# pcb-pick-plaz-led.net
KiCad netlist of a schematic drawn in EAGLE
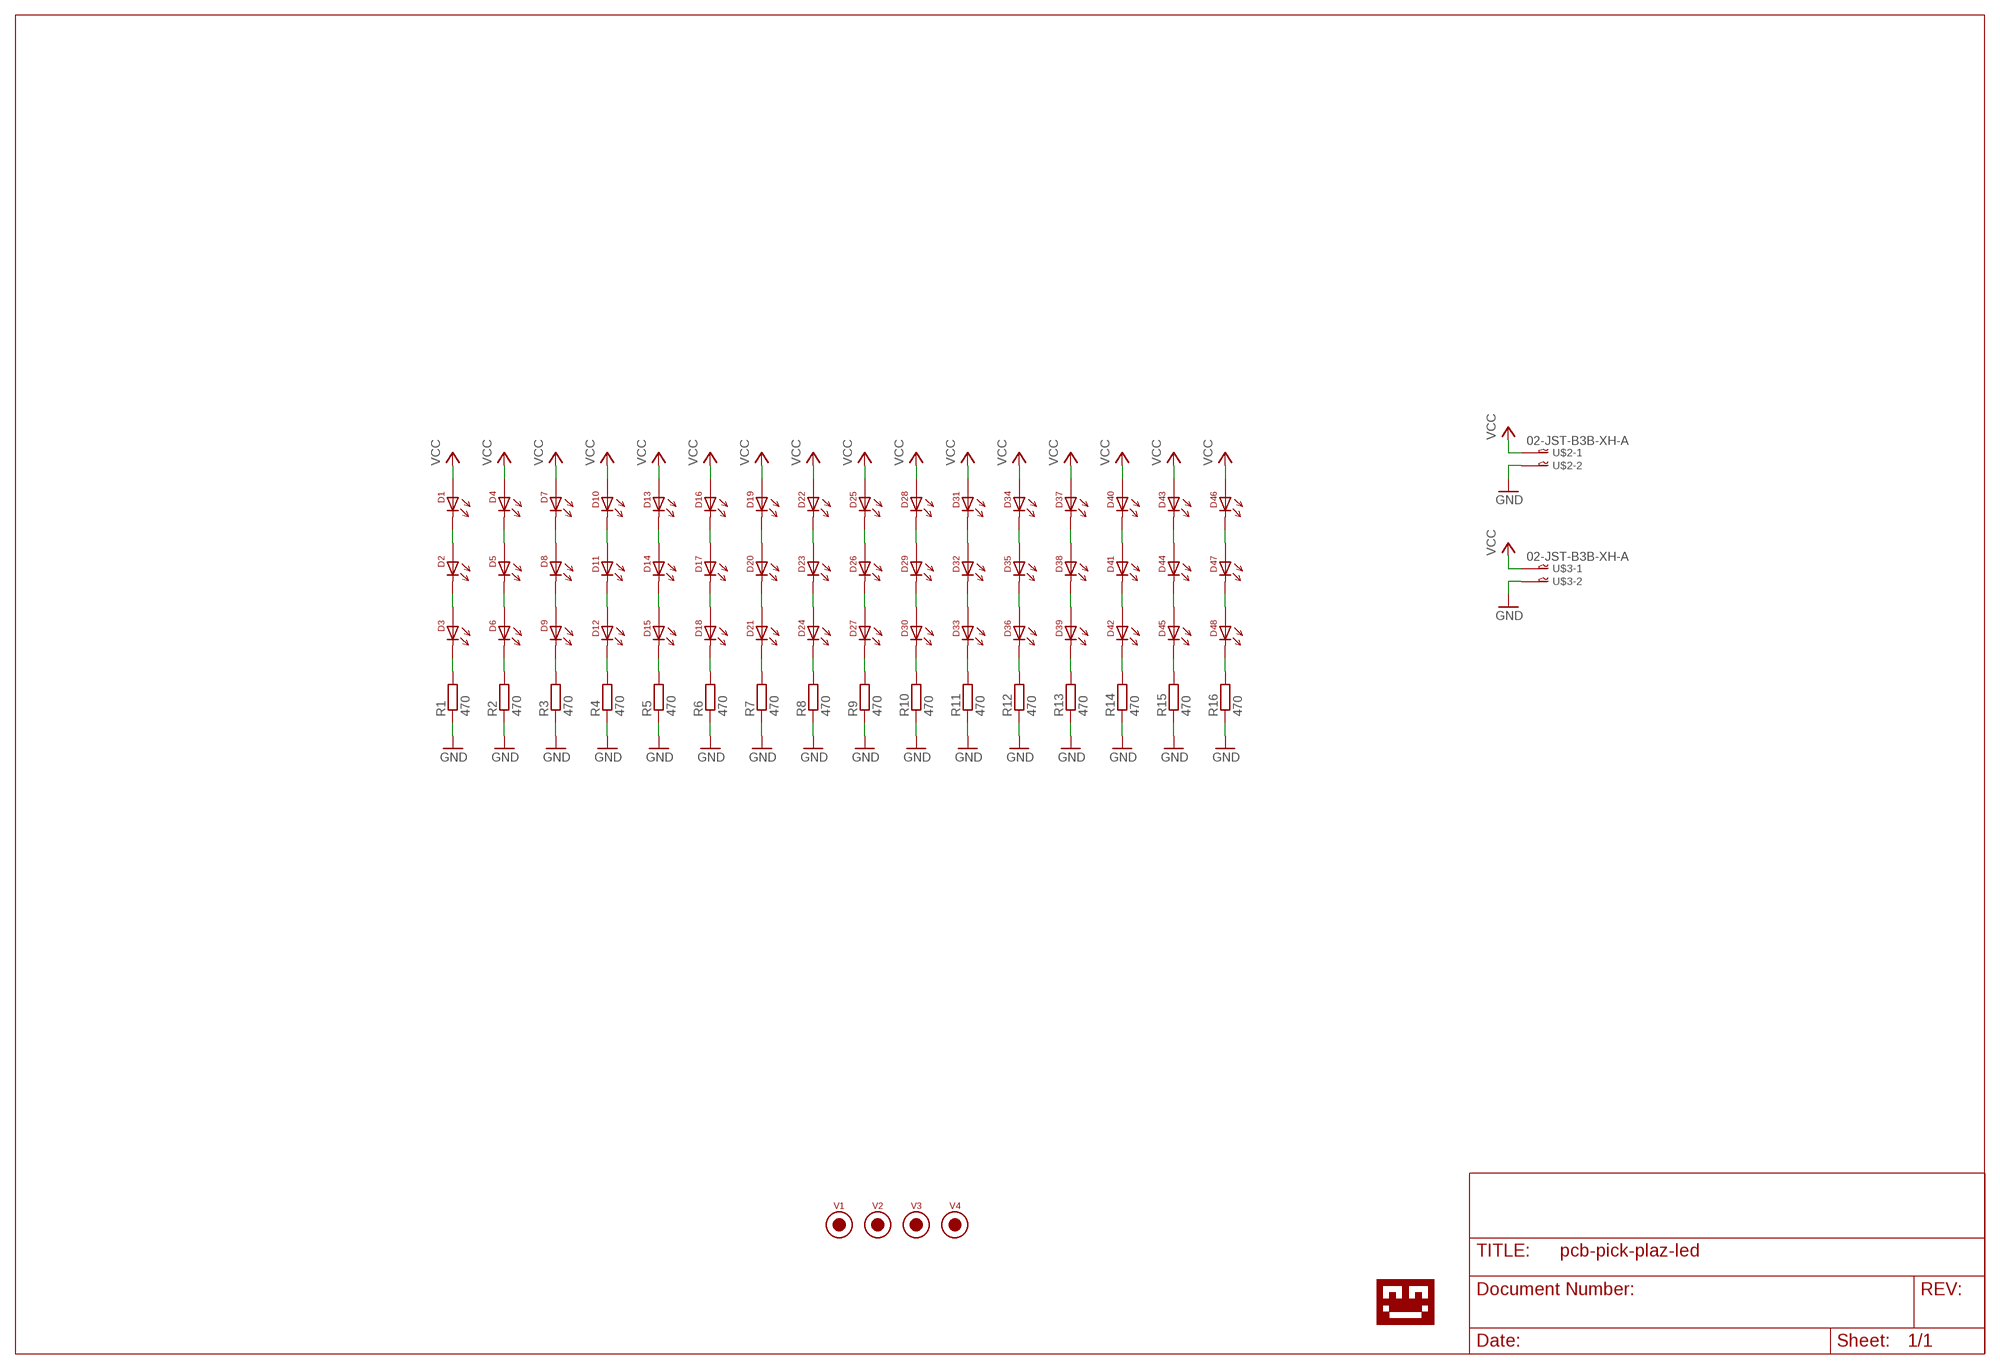
[diagram p0: schematic, sheet 1]

(export (version "E")
  (design (tool "Eeschema 10.0.6"))
  (components
    (comp (ref "D1")
      (value "LED-5730")
      (footprint "eagle-import:5730-LED")
      (libsource (lib "eagle-import") (part "LED-5730"))
    )
    (comp (ref "D2")
      (value "LED-5730")
      (footprint "eagle-import:5730-LED")
      (libsource (lib "eagle-import") (part "LED-5730"))
    )
    (comp (ref "D3")
      (value "LED-5730")
      (footprint "eagle-import:5730-LED")
      (libsource (lib "eagle-import") (part "LED-5730"))
    )
    (comp (ref "D4")
      (value "LED-5730")
      (footprint "eagle-import:5730-LED")
      (libsource (lib "eagle-import") (part "LED-5730"))
    )
    (comp (ref "D5")
      (value "LED-5730")
      (footprint "eagle-import:5730-LED")
      (libsource (lib "eagle-import") (part "LED-5730"))
    )
    (comp (ref "D6")
      (value "LED-5730")
      (footprint "eagle-import:5730-LED")
      (libsource (lib "eagle-import") (part "LED-5730"))
    )
    (comp (ref "D7")
      (value "LED-5730")
      (footprint "eagle-import:5730-LED")
      (libsource (lib "eagle-import") (part "LED-5730"))
    )
    (comp (ref "D8")
      (value "LED-5730")
      (footprint "eagle-import:5730-LED")
      (libsource (lib "eagle-import") (part "LED-5730"))
    )
    (comp (ref "D9")
      (value "LED-5730")
      (footprint "eagle-import:5730-LED")
      (libsource (lib "eagle-import") (part "LED-5730"))
    )
    (comp (ref "D10")
      (value "LED-5730")
      (footprint "eagle-import:5730-LED")
      (libsource (lib "eagle-import") (part "LED-5730"))
    )
    (comp (ref "D11")
      (value "LED-5730")
      (footprint "eagle-import:5730-LED")
      (libsource (lib "eagle-import") (part "LED-5730"))
    )
    (comp (ref "D12")
      (value "LED-5730")
      (footprint "eagle-import:5730-LED")
      (libsource (lib "eagle-import") (part "LED-5730"))
    )
    (comp (ref "D13")
      (value "LED-5730")
      (footprint "eagle-import:5730-LED")
      (libsource (lib "eagle-import") (part "LED-5730"))
    )
    (comp (ref "D14")
      (value "LED-5730")
      (footprint "eagle-import:5730-LED")
      (libsource (lib "eagle-import") (part "LED-5730"))
    )
    (comp (ref "D15")
      (value "LED-5730")
      (footprint "eagle-import:5730-LED")
      (libsource (lib "eagle-import") (part "LED-5730"))
    )
    (comp (ref "D16")
      (value "LED-5730")
      (footprint "eagle-import:5730-LED")
      (libsource (lib "eagle-import") (part "LED-5730"))
    )
    (comp (ref "D17")
      (value "LED-5730")
      (footprint "eagle-import:5730-LED")
      (libsource (lib "eagle-import") (part "LED-5730"))
    )
    (comp (ref "D18")
      (value "LED-5730")
      (footprint "eagle-import:5730-LED")
      (libsource (lib "eagle-import") (part "LED-5730"))
    )
    (comp (ref "D19")
      (value "LED-5730")
      (footprint "eagle-import:5730-LED")
      (libsource (lib "eagle-import") (part "LED-5730"))
    )
    (comp (ref "D20")
      (value "LED-5730")
      (footprint "eagle-import:5730-LED")
      (libsource (lib "eagle-import") (part "LED-5730"))
    )
    (comp (ref "D21")
      (value "LED-5730")
      (footprint "eagle-import:5730-LED")
      (libsource (lib "eagle-import") (part "LED-5730"))
    )
    (comp (ref "D22")
      (value "LED-5730")
      (footprint "eagle-import:5730-LED")
      (libsource (lib "eagle-import") (part "LED-5730"))
    )
    (comp (ref "D23")
      (value "LED-5730")
      (footprint "eagle-import:5730-LED")
      (libsource (lib "eagle-import") (part "LED-5730"))
    )
    (comp (ref "D24")
      (value "LED-5730")
      (footprint "eagle-import:5730-LED")
      (libsource (lib "eagle-import") (part "LED-5730"))
    )
    (comp (ref "D25")
      (value "LED-5730")
      (footprint "eagle-import:5730-LED")
      (libsource (lib "eagle-import") (part "LED-5730"))
    )
    (comp (ref "D26")
      (value "LED-5730")
      (footprint "eagle-import:5730-LED")
      (libsource (lib "eagle-import") (part "LED-5730"))
    )
    (comp (ref "D27")
      (value "LED-5730")
      (footprint "eagle-import:5730-LED")
      (libsource (lib "eagle-import") (part "LED-5730"))
    )
    (comp (ref "D28")
      (value "LED-5730")
      (footprint "eagle-import:5730-LED")
      (libsource (lib "eagle-import") (part "LED-5730"))
    )
    (comp (ref "D29")
      (value "LED-5730")
      (footprint "eagle-import:5730-LED")
      (libsource (lib "eagle-import") (part "LED-5730"))
    )
    (comp (ref "D30")
      (value "LED-5730")
      (footprint "eagle-import:5730-LED")
      (libsource (lib "eagle-import") (part "LED-5730"))
    )
    (comp (ref "D31")
      (value "LED-5730")
      (footprint "eagle-import:5730-LED")
      (libsource (lib "eagle-import") (part "LED-5730"))
    )
    (comp (ref "D32")
      (value "LED-5730")
      (footprint "eagle-import:5730-LED")
      (libsource (lib "eagle-import") (part "LED-5730"))
    )
    (comp (ref "D33")
      (value "LED-5730")
      (footprint "eagle-import:5730-LED")
      (libsource (lib "eagle-import") (part "LED-5730"))
    )
    (comp (ref "D34")
      (value "LED-5730")
      (footprint "eagle-import:5730-LED")
      (libsource (lib "eagle-import") (part "LED-5730"))
    )
    (comp (ref "D35")
      (value "LED-5730")
      (footprint "eagle-import:5730-LED")
      (libsource (lib "eagle-import") (part "LED-5730"))
    )
    (comp (ref "D36")
      (value "LED-5730")
      (footprint "eagle-import:5730-LED")
      (libsource (lib "eagle-import") (part "LED-5730"))
    )
    (comp (ref "D37")
      (value "LED-5730")
      (footprint "eagle-import:5730-LED")
      (libsource (lib "eagle-import") (part "LED-5730"))
    )
    (comp (ref "D38")
      (value "LED-5730")
      (footprint "eagle-import:5730-LED")
      (libsource (lib "eagle-import") (part "LED-5730"))
    )
    (comp (ref "D39")
      (value "LED-5730")
      (footprint "eagle-import:5730-LED")
      (libsource (lib "eagle-import") (part "LED-5730"))
    )
    (comp (ref "D40")
      (value "LED-5730")
      (footprint "eagle-import:5730-LED")
      (libsource (lib "eagle-import") (part "LED-5730"))
    )
    (comp (ref "D41")
      (value "LED-5730")
      (footprint "eagle-import:5730-LED")
      (libsource (lib "eagle-import") (part "LED-5730"))
    )
    (comp (ref "D42")
      (value "LED-5730")
      (footprint "eagle-import:5730-LED")
      (libsource (lib "eagle-import") (part "LED-5730"))
    )
    (comp (ref "D43")
      (value "LED-5730")
      (footprint "eagle-import:5730-LED")
      (libsource (lib "eagle-import") (part "LED-5730"))
    )
    (comp (ref "D44")
      (value "LED-5730")
      (footprint "eagle-import:5730-LED")
      (libsource (lib "eagle-import") (part "LED-5730"))
    )
    (comp (ref "D45")
      (value "LED-5730")
      (footprint "eagle-import:5730-LED")
      (libsource (lib "eagle-import") (part "LED-5730"))
    )
    (comp (ref "D46")
      (value "LED-5730")
      (footprint "eagle-import:5730-LED")
      (libsource (lib "eagle-import") (part "LED-5730"))
    )
    (comp (ref "D47")
      (value "LED-5730")
      (footprint "eagle-import:5730-LED")
      (libsource (lib "eagle-import") (part "LED-5730"))
    )
    (comp (ref "D48")
      (value "LED-5730")
      (footprint "eagle-import:5730-LED")
      (libsource (lib "eagle-import") (part "LED-5730"))
    )
    (comp (ref "R1")
      (value "470")
      (footprint "eagle-import:0805_RES")
      (libsource (lib "eagle-import") (part "RESISTOR0805_RES"))
    )
    (comp (ref "R2")
      (value "470")
      (footprint "eagle-import:0805_RES")
      (libsource (lib "eagle-import") (part "RESISTOR0805_RES"))
    )
    (comp (ref "R3")
      (value "470")
      (footprint "eagle-import:0805_RES")
      (libsource (lib "eagle-import") (part "RESISTOR0805_RES"))
    )
    (comp (ref "R4")
      (value "470")
      (footprint "eagle-import:0805_RES")
      (libsource (lib "eagle-import") (part "RESISTOR0805_RES"))
    )
    (comp (ref "R5")
      (value "470")
      (footprint "eagle-import:0805_RES")
      (libsource (lib "eagle-import") (part "RESISTOR0805_RES"))
    )
    (comp (ref "R6")
      (value "470")
      (footprint "eagle-import:0805_RES")
      (libsource (lib "eagle-import") (part "RESISTOR0805_RES"))
    )
    (comp (ref "R7")
      (value "470")
      (footprint "eagle-import:0805_RES")
      (libsource (lib "eagle-import") (part "RESISTOR0805_RES"))
    )
    (comp (ref "R8")
      (value "470")
      (footprint "eagle-import:0805_RES")
      (libsource (lib "eagle-import") (part "RESISTOR0805_RES"))
    )
    (comp (ref "R9")
      (value "470")
      (footprint "eagle-import:0805_RES")
      (libsource (lib "eagle-import") (part "RESISTOR0805_RES"))
    )
    (comp (ref "R10")
      (value "470")
      (footprint "eagle-import:0805_RES")
      (libsource (lib "eagle-import") (part "RESISTOR0805_RES"))
    )
    (comp (ref "R11")
      (value "470")
      (footprint "eagle-import:0805_RES")
      (libsource (lib "eagle-import") (part "RESISTOR0805_RES"))
    )
    (comp (ref "R12")
      (value "470")
      (footprint "eagle-import:0805_RES")
      (libsource (lib "eagle-import") (part "RESISTOR0805_RES"))
    )
    (comp (ref "R13")
      (value "470")
      (footprint "eagle-import:0805_RES")
      (libsource (lib "eagle-import") (part "RESISTOR0805_RES"))
    )
    (comp (ref "R14")
      (value "470")
      (footprint "eagle-import:0805_RES")
      (libsource (lib "eagle-import") (part "RESISTOR0805_RES"))
    )
    (comp (ref "R15")
      (value "470")
      (footprint "eagle-import:0805_RES")
      (libsource (lib "eagle-import") (part "RESISTOR0805_RES"))
    )
    (comp (ref "R16")
      (value "470")
      (footprint "eagle-import:0805_RES")
      (libsource (lib "eagle-import") (part "RESISTOR0805_RES"))
    )
    (comp (ref "U$1")
      (value "LOGO-TOBENG-1MM-FINISH")
      (footprint "eagle-import:TOBENG-1MM-FINISH")
      (libsource (lib "eagle-import") (part "LOGO-TOBENG-1MM-FINISH"))
    )
    (comp (ref "U$2")
      (value "02-JST-B3B-XH-A")
      (footprint "eagle-import:B2B-XH")
      (libsource (lib "eagle-import") (part "02-JST-B3B-XH-A"))
    )
    (comp (ref "U$3")
      (value "02-JST-B3B-XH-A")
      (footprint "eagle-import:B2B-XH")
      (libsource (lib "eagle-import") (part "02-JST-B3B-XH-A"))
    )
    (comp (ref "V1")
      (value "FIDUCIAL2MM")
      (footprint "eagle-import:FIDUCIAL_2MM")
      (libsource (lib "eagle-import") (part "FIDUCIAL2MM"))
    )
    (comp (ref "V2")
      (value "FIDUCIAL2MM")
      (footprint "eagle-import:FIDUCIAL_2MM")
      (libsource (lib "eagle-import") (part "FIDUCIAL2MM"))
    )
    (comp (ref "V3")
      (value "FIDUCIAL2MM")
      (footprint "eagle-import:FIDUCIAL_2MM")
      (libsource (lib "eagle-import") (part "FIDUCIAL2MM"))
    )
    (comp (ref "V4")
      (value "FIDUCIAL2MM")
      (footprint "eagle-import:FIDUCIAL_2MM")
      (libsource (lib "eagle-import") (part "FIDUCIAL2MM"))
    )
  )
  (nets
    (net (code "1") (name "GND") (class "Default")
      (node (ref "R1") (pin "1") (pinfunction "1_1") (pintype "passive"))
      (node (ref "R10") (pin "1") (pinfunction "1_1") (pintype "passive"))
      (node (ref "R11") (pin "1") (pinfunction "1_1") (pintype "passive"))
      (node (ref "R12") (pin "1") (pinfunction "1_1") (pintype "passive"))
      (node (ref "R13") (pin "1") (pinfunction "1_1") (pintype "passive"))
      (node (ref "R14") (pin "1") (pinfunction "1_1") (pintype "passive"))
      (node (ref "R15") (pin "1") (pinfunction "1_1") (pintype "passive"))
      (node (ref "R16") (pin "1") (pinfunction "1_1") (pintype "passive"))
      (node (ref "R2") (pin "1") (pinfunction "1_1") (pintype "passive"))
      (node (ref "R3") (pin "1") (pinfunction "1_1") (pintype "passive"))
      (node (ref "R4") (pin "1") (pinfunction "1_1") (pintype "passive"))
      (node (ref "R5") (pin "1") (pinfunction "1_1") (pintype "passive"))
      (node (ref "R6") (pin "1") (pinfunction "1_1") (pintype "passive"))
      (node (ref "R7") (pin "1") (pinfunction "1_1") (pintype "passive"))
      (node (ref "R8") (pin "1") (pinfunction "1_1") (pintype "passive"))
      (node (ref "R9") (pin "1") (pinfunction "1_1") (pintype "passive"))
      (node (ref "U$2") (pin "P$2") (pinfunction "1_P$2") (pintype "passive"))
      (node (ref "U$3") (pin "P$2") (pinfunction "1_P$2") (pintype "passive"))
    )
    (net (code "2") (name "Net-(D1-2)") (class "Default")
      (node (ref "D1") (pin "C") (pinfunction "2_C") (pintype "bidirectional"))
      (node (ref "D2") (pin "A1") (pinfunction "1_A1") (pintype "bidirectional"))
      (node (ref "D2") (pin "A2") (pinfunction "1_A2") (pintype "bidirectional"))
    )
    (net (code "3") (name "Net-(D2-2)") (class "Default")
      (node (ref "D2") (pin "C") (pinfunction "2_C") (pintype "bidirectional"))
      (node (ref "D3") (pin "A1") (pinfunction "1_A1") (pintype "bidirectional"))
      (node (ref "D3") (pin "A2") (pinfunction "1_A2") (pintype "bidirectional"))
    )
    (net (code "4") (name "Net-(D3-2)") (class "Default")
      (node (ref "D3") (pin "C") (pinfunction "2_C") (pintype "bidirectional"))
      (node (ref "R1") (pin "2") (pinfunction "2_2") (pintype "passive"))
    )
    (net (code "5") (name "Net-(D4-2)") (class "Default")
      (node (ref "D4") (pin "C") (pinfunction "2_C") (pintype "bidirectional"))
      (node (ref "D5") (pin "A1") (pinfunction "1_A1") (pintype "bidirectional"))
      (node (ref "D5") (pin "A2") (pinfunction "1_A2") (pintype "bidirectional"))
    )
    (net (code "6") (name "Net-(D5-2)") (class "Default")
      (node (ref "D5") (pin "C") (pinfunction "2_C") (pintype "bidirectional"))
      (node (ref "D6") (pin "A1") (pinfunction "1_A1") (pintype "bidirectional"))
      (node (ref "D6") (pin "A2") (pinfunction "1_A2") (pintype "bidirectional"))
    )
    (net (code "7") (name "Net-(D6-2)") (class "Default")
      (node (ref "D6") (pin "C") (pinfunction "2_C") (pintype "bidirectional"))
      (node (ref "R2") (pin "2") (pinfunction "2_2") (pintype "passive"))
    )
    (net (code "8") (name "Net-(D7-2)") (class "Default")
      (node (ref "D7") (pin "C") (pinfunction "2_C") (pintype "bidirectional"))
      (node (ref "D8") (pin "A1") (pinfunction "1_A1") (pintype "bidirectional"))
      (node (ref "D8") (pin "A2") (pinfunction "1_A2") (pintype "bidirectional"))
    )
    (net (code "9") (name "Net-(D8-2)") (class "Default")
      (node (ref "D8") (pin "C") (pinfunction "2_C") (pintype "bidirectional"))
      (node (ref "D9") (pin "A1") (pinfunction "1_A1") (pintype "bidirectional"))
      (node (ref "D9") (pin "A2") (pinfunction "1_A2") (pintype "bidirectional"))
    )
    (net (code "10") (name "Net-(D9-2)") (class "Default")
      (node (ref "D9") (pin "C") (pinfunction "2_C") (pintype "bidirectional"))
      (node (ref "R3") (pin "2") (pinfunction "2_2") (pintype "passive"))
    )
    (net (code "11") (name "Net-(D10-2)") (class "Default")
      (node (ref "D10") (pin "C") (pinfunction "2_C") (pintype "bidirectional"))
      (node (ref "D11") (pin "A1") (pinfunction "1_A1") (pintype "bidirectional"))
      (node (ref "D11") (pin "A2") (pinfunction "1_A2") (pintype "bidirectional"))
    )
    (net (code "12") (name "Net-(D11-2)") (class "Default")
      (node (ref "D11") (pin "C") (pinfunction "2_C") (pintype "bidirectional"))
      (node (ref "D12") (pin "A1") (pinfunction "1_A1") (pintype "bidirectional"))
      (node (ref "D12") (pin "A2") (pinfunction "1_A2") (pintype "bidirectional"))
    )
    (net (code "13") (name "Net-(D12-2)") (class "Default")
      (node (ref "D12") (pin "C") (pinfunction "2_C") (pintype "bidirectional"))
      (node (ref "R4") (pin "2") (pinfunction "2_2") (pintype "passive"))
    )
    (net (code "14") (name "Net-(D13-2)") (class "Default")
      (node (ref "D13") (pin "C") (pinfunction "2_C") (pintype "bidirectional"))
      (node (ref "D14") (pin "A1") (pinfunction "1_A1") (pintype "bidirectional"))
      (node (ref "D14") (pin "A2") (pinfunction "1_A2") (pintype "bidirectional"))
    )
    (net (code "15") (name "Net-(D14-2)") (class "Default")
      (node (ref "D14") (pin "C") (pinfunction "2_C") (pintype "bidirectional"))
      (node (ref "D15") (pin "A1") (pinfunction "1_A1") (pintype "bidirectional"))
      (node (ref "D15") (pin "A2") (pinfunction "1_A2") (pintype "bidirectional"))
    )
    (net (code "16") (name "Net-(D15-2)") (class "Default")
      (node (ref "D15") (pin "C") (pinfunction "2_C") (pintype "bidirectional"))
      (node (ref "R5") (pin "2") (pinfunction "2_2") (pintype "passive"))
    )
    (net (code "17") (name "Net-(D16-2)") (class "Default")
      (node (ref "D16") (pin "C") (pinfunction "2_C") (pintype "bidirectional"))
      (node (ref "D17") (pin "A1") (pinfunction "1_A1") (pintype "bidirectional"))
      (node (ref "D17") (pin "A2") (pinfunction "1_A2") (pintype "bidirectional"))
    )
    (net (code "18") (name "Net-(D17-2)") (class "Default")
      (node (ref "D17") (pin "C") (pinfunction "2_C") (pintype "bidirectional"))
      (node (ref "D18") (pin "A1") (pinfunction "1_A1") (pintype "bidirectional"))
      (node (ref "D18") (pin "A2") (pinfunction "1_A2") (pintype "bidirectional"))
    )
    (net (code "19") (name "Net-(D18-2)") (class "Default")
      (node (ref "D18") (pin "C") (pinfunction "2_C") (pintype "bidirectional"))
      (node (ref "R6") (pin "2") (pinfunction "2_2") (pintype "passive"))
    )
    (net (code "20") (name "Net-(D19-2)") (class "Default")
      (node (ref "D19") (pin "C") (pinfunction "2_C") (pintype "bidirectional"))
      (node (ref "D20") (pin "A1") (pinfunction "1_A1") (pintype "bidirectional"))
      (node (ref "D20") (pin "A2") (pinfunction "1_A2") (pintype "bidirectional"))
    )
    (net (code "21") (name "Net-(D20-2)") (class "Default")
      (node (ref "D20") (pin "C") (pinfunction "2_C") (pintype "bidirectional"))
      (node (ref "D21") (pin "A1") (pinfunction "1_A1") (pintype "bidirectional"))
      (node (ref "D21") (pin "A2") (pinfunction "1_A2") (pintype "bidirectional"))
    )
    (net (code "22") (name "Net-(D21-2)") (class "Default")
      (node (ref "D21") (pin "C") (pinfunction "2_C") (pintype "bidirectional"))
      (node (ref "R7") (pin "2") (pinfunction "2_2") (pintype "passive"))
    )
    (net (code "23") (name "Net-(D22-2)") (class "Default")
      (node (ref "D22") (pin "C") (pinfunction "2_C") (pintype "bidirectional"))
      (node (ref "D23") (pin "A1") (pinfunction "1_A1") (pintype "bidirectional"))
      (node (ref "D23") (pin "A2") (pinfunction "1_A2") (pintype "bidirectional"))
    )
    (net (code "24") (name "Net-(D23-2)") (class "Default")
      (node (ref "D23") (pin "C") (pinfunction "2_C") (pintype "bidirectional"))
      (node (ref "D24") (pin "A1") (pinfunction "1_A1") (pintype "bidirectional"))
      (node (ref "D24") (pin "A2") (pinfunction "1_A2") (pintype "bidirectional"))
    )
    (net (code "25") (name "Net-(D24-2)") (class "Default")
      (node (ref "D24") (pin "C") (pinfunction "2_C") (pintype "bidirectional"))
      (node (ref "R8") (pin "2") (pinfunction "2_2") (pintype "passive"))
    )
    (net (code "26") (name "Net-(D25-2)") (class "Default")
      (node (ref "D25") (pin "C") (pinfunction "2_C") (pintype "bidirectional"))
      (node (ref "D26") (pin "A1") (pinfunction "1_A1") (pintype "bidirectional"))
      (node (ref "D26") (pin "A2") (pinfunction "1_A2") (pintype "bidirectional"))
    )
    (net (code "27") (name "Net-(D26-2)") (class "Default")
      (node (ref "D26") (pin "C") (pinfunction "2_C") (pintype "bidirectional"))
      (node (ref "D27") (pin "A1") (pinfunction "1_A1") (pintype "bidirectional"))
      (node (ref "D27") (pin "A2") (pinfunction "1_A2") (pintype "bidirectional"))
    )
    (net (code "28") (name "Net-(D27-2)") (class "Default")
      (node (ref "D27") (pin "C") (pinfunction "2_C") (pintype "bidirectional"))
      (node (ref "R9") (pin "2") (pinfunction "2_2") (pintype "passive"))
    )
    (net (code "29") (name "Net-(D28-2)") (class "Default")
      (node (ref "D28") (pin "C") (pinfunction "2_C") (pintype "bidirectional"))
      (node (ref "D29") (pin "A1") (pinfunction "1_A1") (pintype "bidirectional"))
      (node (ref "D29") (pin "A2") (pinfunction "1_A2") (pintype "bidirectional"))
    )
    (net (code "30") (name "Net-(D29-2)") (class "Default")
      (node (ref "D29") (pin "C") (pinfunction "2_C") (pintype "bidirectional"))
      (node (ref "D30") (pin "A1") (pinfunction "1_A1") (pintype "bidirectional"))
      (node (ref "D30") (pin "A2") (pinfunction "1_A2") (pintype "bidirectional"))
    )
    (net (code "31") (name "Net-(D30-2)") (class "Default")
      (node (ref "D30") (pin "C") (pinfunction "2_C") (pintype "bidirectional"))
      (node (ref "R10") (pin "2") (pinfunction "2_2") (pintype "passive"))
    )
    (net (code "32") (name "Net-(D31-2)") (class "Default")
      (node (ref "D31") (pin "C") (pinfunction "2_C") (pintype "bidirectional"))
      (node (ref "D32") (pin "A1") (pinfunction "1_A1") (pintype "bidirectional"))
      (node (ref "D32") (pin "A2") (pinfunction "1_A2") (pintype "bidirectional"))
    )
    (net (code "33") (name "Net-(D32-2)") (class "Default")
      (node (ref "D32") (pin "C") (pinfunction "2_C") (pintype "bidirectional"))
      (node (ref "D33") (pin "A1") (pinfunction "1_A1") (pintype "bidirectional"))
      (node (ref "D33") (pin "A2") (pinfunction "1_A2") (pintype "bidirectional"))
    )
    (net (code "34") (name "Net-(D33-2)") (class "Default")
      (node (ref "D33") (pin "C") (pinfunction "2_C") (pintype "bidirectional"))
      (node (ref "R11") (pin "2") (pinfunction "2_2") (pintype "passive"))
    )
    (net (code "35") (name "Net-(D34-2)") (class "Default")
      (node (ref "D34") (pin "C") (pinfunction "2_C") (pintype "bidirectional"))
      (node (ref "D35") (pin "A1") (pinfunction "1_A1") (pintype "bidirectional"))
      (node (ref "D35") (pin "A2") (pinfunction "1_A2") (pintype "bidirectional"))
    )
    (net (code "36") (name "Net-(D35-2)") (class "Default")
      (node (ref "D35") (pin "C") (pinfunction "2_C") (pintype "bidirectional"))
      (node (ref "D36") (pin "A1") (pinfunction "1_A1") (pintype "bidirectional"))
      (node (ref "D36") (pin "A2") (pinfunction "1_A2") (pintype "bidirectional"))
    )
    (net (code "37") (name "Net-(D36-2)") (class "Default")
      (node (ref "D36") (pin "C") (pinfunction "2_C") (pintype "bidirectional"))
      (node (ref "R12") (pin "2") (pinfunction "2_2") (pintype "passive"))
    )
    (net (code "38") (name "Net-(D37-2)") (class "Default")
      (node (ref "D37") (pin "C") (pinfunction "2_C") (pintype "bidirectional"))
      (node (ref "D38") (pin "A1") (pinfunction "1_A1") (pintype "bidirectional"))
      (node (ref "D38") (pin "A2") (pinfunction "1_A2") (pintype "bidirectional"))
    )
    (net (code "39") (name "Net-(D38-2)") (class "Default")
      (node (ref "D38") (pin "C") (pinfunction "2_C") (pintype "bidirectional"))
      (node (ref "D39") (pin "A1") (pinfunction "1_A1") (pintype "bidirectional"))
      (node (ref "D39") (pin "A2") (pinfunction "1_A2") (pintype "bidirectional"))
    )
    (net (code "40") (name "Net-(D39-2)") (class "Default")
      (node (ref "D39") (pin "C") (pinfunction "2_C") (pintype "bidirectional"))
      (node (ref "R13") (pin "2") (pinfunction "2_2") (pintype "passive"))
    )
    (net (code "41") (name "Net-(D40-2)") (class "Default")
      (node (ref "D40") (pin "C") (pinfunction "2_C") (pintype "bidirectional"))
      (node (ref "D41") (pin "A1") (pinfunction "1_A1") (pintype "bidirectional"))
      (node (ref "D41") (pin "A2") (pinfunction "1_A2") (pintype "bidirectional"))
    )
    (net (code "42") (name "Net-(D41-2)") (class "Default")
      (node (ref "D41") (pin "C") (pinfunction "2_C") (pintype "bidirectional"))
      (node (ref "D42") (pin "A1") (pinfunction "1_A1") (pintype "bidirectional"))
      (node (ref "D42") (pin "A2") (pinfunction "1_A2") (pintype "bidirectional"))
    )
    (net (code "43") (name "Net-(D42-2)") (class "Default")
      (node (ref "D42") (pin "C") (pinfunction "2_C") (pintype "bidirectional"))
      (node (ref "R14") (pin "2") (pinfunction "2_2") (pintype "passive"))
    )
    (net (code "44") (name "Net-(D43-2)") (class "Default")
      (node (ref "D43") (pin "C") (pinfunction "2_C") (pintype "bidirectional"))
      (node (ref "D44") (pin "A1") (pinfunction "1_A1") (pintype "bidirectional"))
      (node (ref "D44") (pin "A2") (pinfunction "1_A2") (pintype "bidirectional"))
    )
    (net (code "45") (name "Net-(D44-2)") (class "Default")
      (node (ref "D44") (pin "C") (pinfunction "2_C") (pintype "bidirectional"))
      (node (ref "D45") (pin "A1") (pinfunction "1_A1") (pintype "bidirectional"))
      (node (ref "D45") (pin "A2") (pinfunction "1_A2") (pintype "bidirectional"))
    )
    (net (code "46") (name "Net-(D45-2)") (class "Default")
      (node (ref "D45") (pin "C") (pinfunction "2_C") (pintype "bidirectional"))
      (node (ref "R15") (pin "2") (pinfunction "2_2") (pintype "passive"))
    )
    (net (code "47") (name "Net-(D46-2)") (class "Default")
      (node (ref "D46") (pin "C") (pinfunction "2_C") (pintype "bidirectional"))
      (node (ref "D47") (pin "A1") (pinfunction "1_A1") (pintype "bidirectional"))
      (node (ref "D47") (pin "A2") (pinfunction "1_A2") (pintype "bidirectional"))
    )
    (net (code "48") (name "Net-(D47-2)") (class "Default")
      (node (ref "D47") (pin "C") (pinfunction "2_C") (pintype "bidirectional"))
      (node (ref "D48") (pin "A1") (pinfunction "1_A1") (pintype "bidirectional"))
      (node (ref "D48") (pin "A2") (pinfunction "1_A2") (pintype "bidirectional"))
    )
    (net (code "49") (name "Net-(D48-2)") (class "Default")
      (node (ref "D48") (pin "C") (pinfunction "2_C") (pintype "bidirectional"))
      (node (ref "R16") (pin "2") (pinfunction "2_2") (pintype "passive"))
    )
    (net (code "50") (name "VCC") (class "Default")
      (node (ref "D1") (pin "A1") (pinfunction "1_A1") (pintype "bidirectional"))
      (node (ref "D1") (pin "A2") (pinfunction "1_A2") (pintype "bidirectional"))
      (node (ref "D10") (pin "A1") (pinfunction "1_A1") (pintype "bidirectional"))
      (node (ref "D10") (pin "A2") (pinfunction "1_A2") (pintype "bidirectional"))
      (node (ref "D13") (pin "A1") (pinfunction "1_A1") (pintype "bidirectional"))
      (node (ref "D13") (pin "A2") (pinfunction "1_A2") (pintype "bidirectional"))
      (node (ref "D16") (pin "A1") (pinfunction "1_A1") (pintype "bidirectional"))
      (node (ref "D16") (pin "A2") (pinfunction "1_A2") (pintype "bidirectional"))
      (node (ref "D19") (pin "A1") (pinfunction "1_A1") (pintype "bidirectional"))
      (node (ref "D19") (pin "A2") (pinfunction "1_A2") (pintype "bidirectional"))
      (node (ref "D22") (pin "A1") (pinfunction "1_A1") (pintype "bidirectional"))
      (node (ref "D22") (pin "A2") (pinfunction "1_A2") (pintype "bidirectional"))
      (node (ref "D25") (pin "A1") (pinfunction "1_A1") (pintype "bidirectional"))
      (node (ref "D25") (pin "A2") (pinfunction "1_A2") (pintype "bidirectional"))
      (node (ref "D28") (pin "A1") (pinfunction "1_A1") (pintype "bidirectional"))
      (node (ref "D28") (pin "A2") (pinfunction "1_A2") (pintype "bidirectional"))
      (node (ref "D31") (pin "A1") (pinfunction "1_A1") (pintype "bidirectional"))
      (node (ref "D31") (pin "A2") (pinfunction "1_A2") (pintype "bidirectional"))
      (node (ref "D34") (pin "A1") (pinfunction "1_A1") (pintype "bidirectional"))
      (node (ref "D34") (pin "A2") (pinfunction "1_A2") (pintype "bidirectional"))
      (node (ref "D37") (pin "A1") (pinfunction "1_A1") (pintype "bidirectional"))
      (node (ref "D37") (pin "A2") (pinfunction "1_A2") (pintype "bidirectional"))
      (node (ref "D4") (pin "A1") (pinfunction "1_A1") (pintype "bidirectional"))
      (node (ref "D4") (pin "A2") (pinfunction "1_A2") (pintype "bidirectional"))
      (node (ref "D40") (pin "A1") (pinfunction "1_A1") (pintype "bidirectional"))
      (node (ref "D40") (pin "A2") (pinfunction "1_A2") (pintype "bidirectional"))
      (node (ref "D43") (pin "A1") (pinfunction "1_A1") (pintype "bidirectional"))
      (node (ref "D43") (pin "A2") (pinfunction "1_A2") (pintype "bidirectional"))
      (node (ref "D46") (pin "A1") (pinfunction "1_A1") (pintype "bidirectional"))
      (node (ref "D46") (pin "A2") (pinfunction "1_A2") (pintype "bidirectional"))
      (node (ref "D7") (pin "A1") (pinfunction "1_A1") (pintype "bidirectional"))
      (node (ref "D7") (pin "A2") (pinfunction "1_A2") (pintype "bidirectional"))
      (node (ref "U$2") (pin "P$1") (pinfunction "1_P$1") (pintype "passive"))
      (node (ref "U$3") (pin "P$1") (pinfunction "1_P$1") (pintype "passive"))
    )
  )
)
